# mippe_mod.net
KiCad netlist of a schematic drawn in EAGLE
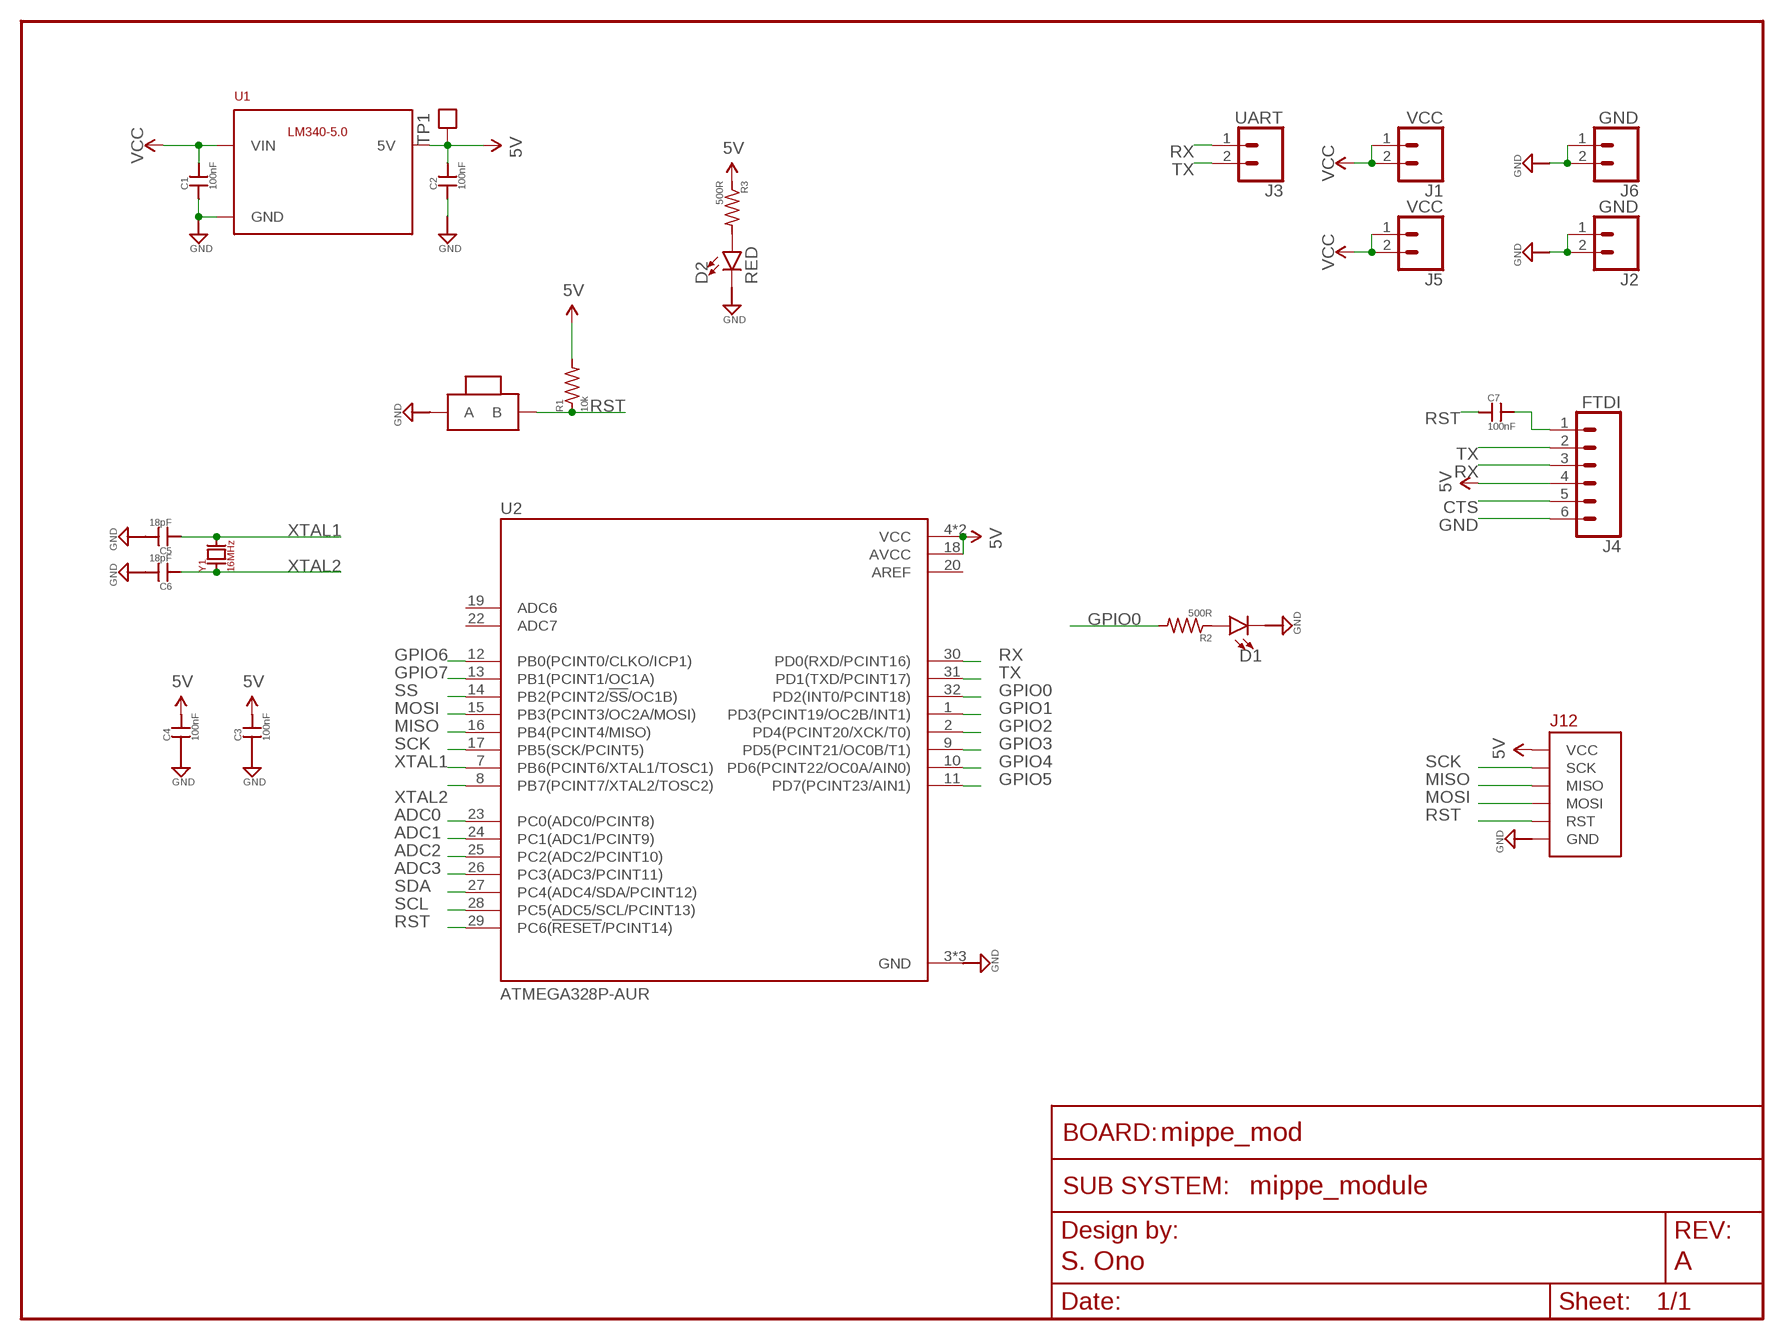
[diagram p0: schematic, sheet 1]

(export (version "E")
  (design (tool "Eeschema 10.0.6"))
  (components
    (comp (ref "C1")
      (value "100nF")
      (footprint "eagle-import:0402-CAP")
      (libsource (lib "eagle-import") (part "CAP0402-CAP"))
    )
    (comp (ref "C2")
      (value "100nF")
      (footprint "eagle-import:0402-CAP")
      (libsource (lib "eagle-import") (part "CAP0402-CAP"))
    )
    (comp (ref "C3")
      (value "100nF")
      (footprint "eagle-import:0402-CAP")
      (libsource (lib "eagle-import") (part "CAP0402-CAP"))
    )
    (comp (ref "C4")
      (value "100nF")
      (footprint "eagle-import:0402-CAP")
      (libsource (lib "eagle-import") (part "CAP0402-CAP"))
    )
    (comp (ref "C5")
      (value "18pF")
      (footprint "eagle-import:0402-CAP")
      (libsource (lib "eagle-import") (part "CAP0402-CAP"))
    )
    (comp (ref "C6")
      (value "18pF")
      (footprint "eagle-import:0402-CAP")
      (libsource (lib "eagle-import") (part "CAP0402-CAP"))
    )
    (comp (ref "C7")
      (value "100nF")
      (footprint "eagle-import:0402-CAP")
      (libsource (lib "eagle-import") (part "CAP0402-CAP"))
    )
    (comp (ref "D1")
      (value "LED0603")
      (footprint "eagle-import:LED-0603")
      (libsource (lib "eagle-import") (part "LED0603"))
    )
    (comp (ref "D2")
      (value "RED")
      (footprint "eagle-import:LED-0603")
      (libsource (lib "eagle-import") (part "LED0603"))
    )
    (comp (ref "J1")
      (value "VCC")
      (footprint "eagle-import:1X02")
      (libsource (lib "eagle-import") (part "CONN_02"))
    )
    (comp (ref "J2")
      (value "GND")
      (footprint "eagle-import:1X02")
      (libsource (lib "eagle-import") (part "CONN_02"))
    )
    (comp (ref "J3")
      (value "UART")
      (footprint "eagle-import:1X02")
      (libsource (lib "eagle-import") (part "CONN_02"))
    )
    (comp (ref "J4")
      (value "FTDI")
      (footprint "eagle-import:1X06_NO_SILK")
      (libsource (lib "eagle-import") (part "CONN_06NO_SILK_FEMALE_PTH"))
    )
    (comp (ref "J5")
      (value "VCC")
      (footprint "eagle-import:1X02")
      (libsource (lib "eagle-import") (part "CONN_02"))
    )
    (comp (ref "J6")
      (value "GND")
      (footprint "eagle-import:1X02")
      (libsource (lib "eagle-import") (part "CONN_02"))
    )
    (comp (ref "J12")
      (value "BURNIN")
      (footprint "eagle-import:BURNIN")
      (libsource (lib "eagle-import") (part "BURNIN"))
    )
    (comp (ref "R1")
      (value "10k")
      (footprint "eagle-import:R0402")
      (libsource (lib "eagle-import") (part "R-US_R0402"))
    )
    (comp (ref "R2")
      (value "500R")
      (footprint "eagle-import:R0402")
      (libsource (lib "eagle-import") (part "R-US_R0402"))
    )
    (comp (ref "R3")
      (value "500R")
      (footprint "eagle-import:R0402")
      (libsource (lib "eagle-import") (part "R-US_R0402"))
    )
    (comp (ref "SW1")
      (value "BTN-PTS810")
      (footprint "eagle-import:BTN_PTS810")
      (libsource (lib "eagle-import") (part "BTN-PTS810"))
    )
    (comp (ref "TP1")
      (value "TEST_POINTTHRU")
      (footprint "eagle-import:TEST_POINT")
      (libsource (lib "eagle-import") (part "TEST_POINTTHRU"))
    )
    (comp (ref "U1")
      (value "LM340MPX-5.0230")
      (footprint "eagle-import:SOT230P700X180-4N")
      (libsource (lib "eagle-import") (part "LM340MPX-5.0230"))
    )
    (comp (ref "U2")
      (value "ATMEGA328P-AUR")
      (footprint "eagle-import:QFP80P900X900X120-32N")
      (fields (field (name "DIGI-KEY_PART_NUMBER") "ATMEGA328P-AURCT-ND") (field (name "MF") "Microchip"))
      (libsource (lib "eagle-import") (part "ATMEGA328P-AUR"))
    )
    (comp (ref "Y1")
      (value "16MHz")
      (footprint "eagle-import:XTAL500X320X130N")
      (libsource (lib "eagle-import") (part "CRYSTAL_SMOL"))
    )
  )
  (nets
    (net (code "1") (name "/ADC0") (class "Default")
      (node (ref "U2") (pin "23") (pinfunction "PC0(ADC0/PCINT8)_23") (pintype "bidirectional"))
    )
    (net (code "2") (name "/ADC1") (class "Default")
      (node (ref "U2") (pin "24") (pinfunction "PC1(ADC1/PCINT9)_24") (pintype "bidirectional"))
    )
    (net (code "3") (name "/ADC2") (class "Default")
      (node (ref "U2") (pin "25") (pinfunction "PC2(ADC2/PCINT10)_25") (pintype "bidirectional"))
    )
    (net (code "4") (name "/ADC3") (class "Default")
      (node (ref "U2") (pin "26") (pinfunction "PC3(ADC3/PCINT11)_26") (pintype "bidirectional"))
    )
    (net (code "5") (name "/AREF") (class "Default")
      (node (ref "U2") (pin "20") (pinfunction "AREF_20") (pintype "power_in"))
    )
    (net (code "6") (name "/CTS") (class "Default")
      (node (ref "J4") (pin "5") (pinfunction "5_5") (pintype "passive"))
    )
    (net (code "7") (name "/GPIO0") (class "Default")
      (node (ref "R2") (pin "2") (pinfunction "2_2") (pintype "passive"))
      (node (ref "U2") (pin "32") (pinfunction "PD2(INT0/PCINT18)_32") (pintype "bidirectional"))
    )
    (net (code "8") (name "/GPIO1") (class "Default")
      (node (ref "U2") (pin "1") (pinfunction "PD3(PCINT19/OC2B/INT1)_1") (pintype "bidirectional"))
    )
    (net (code "9") (name "/GPIO2") (class "Default")
      (node (ref "U2") (pin "2") (pinfunction "PD4(PCINT20/XCK/T0)_2") (pintype "bidirectional"))
    )
    (net (code "10") (name "/GPIO3") (class "Default")
      (node (ref "U2") (pin "9") (pinfunction "PD5(PCINT21/OC0B/T1)_9") (pintype "bidirectional"))
    )
    (net (code "11") (name "/GPIO4") (class "Default")
      (node (ref "U2") (pin "10") (pinfunction "PD6(PCINT22/OC0A/AIN0)_10") (pintype "bidirectional"))
    )
    (net (code "12") (name "/GPIO5") (class "Default")
      (node (ref "U2") (pin "11") (pinfunction "PD7(PCINT23/AIN1)_11") (pintype "bidirectional"))
    )
    (net (code "13") (name "/GPIO6") (class "Default")
      (node (ref "U2") (pin "12") (pinfunction "PB0(PCINT0/CLKO/ICP1)_12") (pintype "bidirectional"))
    )
    (net (code "14") (name "/GPIO7") (class "Default")
      (node (ref "U2") (pin "13") (pinfunction "PB1(PCINT1/OC1A)_13") (pintype "bidirectional"))
    )
    (net (code "15") (name "/MISO") (class "Default")
      (node (ref "J12") (pin "MISO") (pinfunction "MISO_MISO") (pintype "bidirectional"))
      (node (ref "U2") (pin "16") (pinfunction "PB4(PCINT4/MISO)_16") (pintype "bidirectional"))
    )
    (net (code "16") (name "/MOSI") (class "Default")
      (node (ref "J12") (pin "MOSI") (pinfunction "MOSI_MOSI") (pintype "bidirectional"))
      (node (ref "U2") (pin "15") (pinfunction "PB3(PCINT3/OC2A/MOSI)_15") (pintype "bidirectional"))
    )
    (net (code "17") (name "/RST") (class "Default")
      (node (ref "C7") (pin "1") (pinfunction "1_1") (pintype "passive"))
      (node (ref "J12") (pin "RST") (pinfunction "RST_RST") (pintype "bidirectional"))
      (node (ref "R1") (pin "1") (pinfunction "1_1") (pintype "passive"))
      (node (ref "SW1") (pin "3") (pinfunction "B_3") (pintype "bidirectional"))
      (node (ref "SW1") (pin "4") (pinfunction "B_4") (pintype "bidirectional"))
      (node (ref "U2") (pin "29") (pinfunction "PC6(~{RESET}/PCINT14)_29") (pintype "bidirectional"))
    )
    (net (code "18") (name "/RX") (class "Default")
      (node (ref "J3") (pin "1") (pinfunction "1_1") (pintype "passive"))
      (node (ref "J4") (pin "3") (pinfunction "3_3") (pintype "passive"))
      (node (ref "U2") (pin "30") (pinfunction "PD0(RXD/PCINT16)_30") (pintype "bidirectional"))
    )
    (net (code "19") (name "/SCK") (class "Default")
      (node (ref "J12") (pin "SCK") (pinfunction "SCK_SCK") (pintype "bidirectional"))
      (node (ref "U2") (pin "17") (pinfunction "PB5(SCK/PCINT5)_17") (pintype "bidirectional"))
    )
    (net (code "20") (name "/SCL") (class "Default")
      (node (ref "U2") (pin "28") (pinfunction "PC5(ADC5/SCL/PCINT13)_28") (pintype "bidirectional"))
    )
    (net (code "21") (name "/SDA") (class "Default")
      (node (ref "U2") (pin "27") (pinfunction "PC4(ADC4/SDA/PCINT12)_27") (pintype "bidirectional"))
    )
    (net (code "22") (name "/SS") (class "Default")
      (node (ref "U2") (pin "14") (pinfunction "PB2(PCINT2/~{SS}/OC1B)_14") (pintype "bidirectional"))
    )
    (net (code "23") (name "/TX") (class "Default")
      (node (ref "J3") (pin "2") (pinfunction "2_2") (pintype "passive"))
      (node (ref "J4") (pin "2") (pinfunction "2_2") (pintype "passive"))
      (node (ref "U2") (pin "31") (pinfunction "PD1(TXD/PCINT17)_31") (pintype "bidirectional"))
    )
    (net (code "24") (name "/XTAL1") (class "Default")
      (node (ref "C5") (pin "1") (pinfunction "1_1") (pintype "passive"))
      (node (ref "U2") (pin "7") (pinfunction "PB6(PCINT6/XTAL1/TOSC1)_7") (pintype "bidirectional"))
      (node (ref "Y1") (pin "2") (pinfunction "B_2") (pintype "passive"))
    )
    (net (code "25") (name "/XTAL2") (class "Default")
      (node (ref "C6") (pin "1") (pinfunction "1_1") (pintype "passive"))
      (node (ref "U2") (pin "8") (pinfunction "PB7(PCINT7/XTAL2/TOSC2)_8") (pintype "bidirectional"))
      (node (ref "Y1") (pin "1") (pinfunction "A_1") (pintype "passive"))
    )
    (net (code "26") (name "5V") (class "Default")
      (node (ref "C2") (pin "2") (pinfunction "2_2") (pintype "passive"))
      (node (ref "C3") (pin "2") (pinfunction "2_2") (pintype "passive"))
      (node (ref "C4") (pin "2") (pinfunction "2_2") (pintype "passive"))
      (node (ref "J12") (pin "3.3V") (pinfunction "VCC_3.3V") (pintype "power_in"))
      (node (ref "J4") (pin "4") (pinfunction "4_4") (pintype "passive"))
      (node (ref "R1") (pin "2") (pinfunction "2_2") (pintype "passive"))
      (node (ref "R3") (pin "1") (pinfunction "1_1") (pintype "passive"))
      (node (ref "TP1") (pin "1") (pinfunction "P$1_1") (pintype "bidirectional"))
      (node (ref "U1") (pin "3") (pinfunction "5V_3") (pintype "power_in"))
      (node (ref "U2") (pin "18") (pinfunction "AVCC_18") (pintype "power_in"))
      (node (ref "U2") (pin "4") (pinfunction "VCC_4") (pintype "power_in"))
      (node (ref "U2") (pin "6") (pinfunction "VCC_6") (pintype "power_in"))
    )
    (net (code "27") (name "GND") (class "Default")
      (node (ref "C1") (pin "1") (pinfunction "1_1") (pintype "passive"))
      (node (ref "C2") (pin "1") (pinfunction "1_1") (pintype "passive"))
      (node (ref "C3") (pin "1") (pinfunction "1_1") (pintype "passive"))
      (node (ref "C4") (pin "1") (pinfunction "1_1") (pintype "passive"))
      (node (ref "C5") (pin "2") (pinfunction "2_2") (pintype "passive"))
      (node (ref "C6") (pin "2") (pinfunction "2_2") (pintype "passive"))
      (node (ref "D1") (pin "C") (pinfunction "C_C") (pintype "passive"))
      (node (ref "D2") (pin "C") (pinfunction "C_C") (pintype "passive"))
      (node (ref "J12") (pin "GND") (pinfunction "GND_GND") (pintype "power_in"))
      (node (ref "J2") (pin "1") (pinfunction "1_1") (pintype "passive"))
      (node (ref "J2") (pin "2") (pinfunction "2_2") (pintype "passive"))
      (node (ref "J4") (pin "6") (pinfunction "6_6") (pintype "passive"))
      (node (ref "J6") (pin "1") (pinfunction "1_1") (pintype "passive"))
      (node (ref "J6") (pin "2") (pinfunction "2_2") (pintype "passive"))
      (node (ref "SW1") (pin "1") (pinfunction "A_1") (pintype "bidirectional"))
      (node (ref "SW1") (pin "2") (pinfunction "A_2") (pintype "bidirectional"))
      (node (ref "U1") (pin "2") (pinfunction "GND_2") (pintype "power_in"))
      (node (ref "U1") (pin "4") (pinfunction "GND_4") (pintype "power_in"))
      (node (ref "U2") (pin "21") (pinfunction "GND_21") (pintype "power_in"))
      (node (ref "U2") (pin "3") (pinfunction "GND_3") (pintype "power_in"))
      (node (ref "U2") (pin "5") (pinfunction "GND_5") (pintype "power_in"))
    )
    (net (code "28") (name "Net-(C7-Pad2)") (class "Default")
      (node (ref "C7") (pin "2") (pinfunction "2_2") (pintype "passive"))
      (node (ref "J4") (pin "1") (pinfunction "1_1") (pintype "passive"))
    )
    (net (code "29") (name "Net-(D1-PadA)") (class "Default")
      (node (ref "D1") (pin "A") (pinfunction "A_A") (pintype "passive"))
      (node (ref "R2") (pin "1") (pinfunction "1_1") (pintype "passive"))
    )
    (net (code "30") (name "Net-(D2-PadA)") (class "Default")
      (node (ref "D2") (pin "A") (pinfunction "A_A") (pintype "passive"))
      (node (ref "R3") (pin "2") (pinfunction "2_2") (pintype "passive"))
    )
    (net (code "31") (name "VCC") (class "Default")
      (node (ref "C1") (pin "2") (pinfunction "2_2") (pintype "passive"))
      (node (ref "J1") (pin "1") (pinfunction "1_1") (pintype "passive"))
      (node (ref "J1") (pin "2") (pinfunction "2_2") (pintype "passive"))
      (node (ref "J5") (pin "1") (pinfunction "1_1") (pintype "passive"))
      (node (ref "J5") (pin "2") (pinfunction "2_2") (pintype "passive"))
      (node (ref "U1") (pin "1") (pinfunction "VIN_1") (pintype "power_in"))
    )
    (net (code "32") (name "unconnected-(U2-ADC6-Pad19)") (class "Default")
      (node (ref "U2") (pin "19") (pinfunction "ADC6_19") (pintype "input"))
    )
    (net (code "33") (name "unconnected-(U2-ADC7-Pad22)") (class "Default")
      (node (ref "U2") (pin "22") (pinfunction "ADC7_22") (pintype "input"))
    )
  )
)
